# dcdc0210.net
KiCad netlist of a schematic drawn in EAGLE
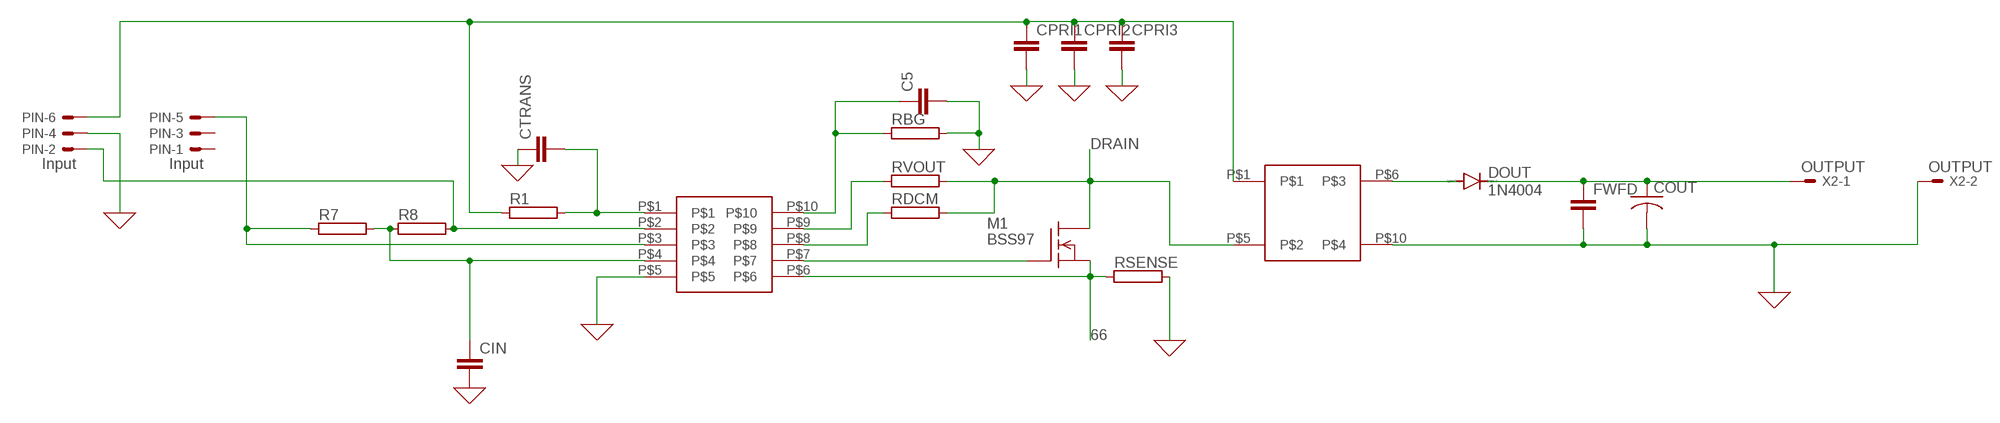
[diagram p0: schematic, sheet 1]

(export (version "E")
  (design (tool "Eeschema 10.0.6"))
  (components
    (comp (ref "C5")
      (value "C5/3.5")
      (footprint "eagle-import:C5B3.5")
      (libsource (lib "eagle-import") (part "C5/3.5"))
    )
    (comp (ref "CIN")
      (value "C5/3.5")
      (footprint "eagle-import:C5B3.5")
      (libsource (lib "eagle-import") (part "C5/3.5"))
    )
    (comp (ref "COUT")
      (value "C-US050-050X075")
      (footprint "eagle-import:C050-050X075")
      (libsource (lib "eagle-import") (part "C-US050-050X075"))
    )
    (comp (ref "CPRI1")
      (value "C5/3.5")
      (footprint "eagle-import:C5B3.5")
      (libsource (lib "eagle-import") (part "C5/3.5"))
    )
    (comp (ref "CPRI2")
      (value "C5/3.5")
      (footprint "eagle-import:C5B3.5")
      (libsource (lib "eagle-import") (part "C5/3.5"))
    )
    (comp (ref "CPRI3")
      (value "C5/3.5")
      (footprint "eagle-import:C5B3.5")
      (libsource (lib "eagle-import") (part "C5/3.5"))
    )
    (comp (ref "CTRANS")
      (value "C5/3.5")
      (footprint "eagle-import:C5B3.5")
      (libsource (lib "eagle-import") (part "C5/3.5"))
    )
    (comp (ref "DOUT")
      (value "1N4004")
      (footprint "eagle-import:DO41-10")
      (libsource (lib "eagle-import") (part "1N4004"))
    )
    (comp (ref "FWFD")
      (value "C5/3.5")
      (footprint "eagle-import:C5B3.5")
      (libsource (lib "eagle-import") (part "C5/3.5"))
    )
    (comp (ref "M1")
      (value "BSS97")
      (footprint "eagle-import:TO202")
      (libsource (lib "eagle-import") (part "BSS97"))
    )
    (comp (ref "PIN")
      (value "Input")
      (footprint "eagle-import:332-06")
      (libsource (lib "eagle-import") (part "332-06"))
    )
    (comp (ref "R1")
      (value "RAC01")
      (footprint "eagle-import:AC01")
      (libsource (lib "eagle-import") (part "RAC01"))
    )
    (comp (ref "R7")
      (value "RAC01")
      (footprint "eagle-import:AC01")
      (libsource (lib "eagle-import") (part "RAC01"))
    )
    (comp (ref "R8")
      (value "RAC01")
      (footprint "eagle-import:AC01")
      (libsource (lib "eagle-import") (part "RAC01"))
    )
    (comp (ref "RBG")
      (value "RAC01")
      (footprint "eagle-import:AC01")
      (libsource (lib "eagle-import") (part "RAC01"))
    )
    (comp (ref "RDCM")
      (value "RAC01")
      (footprint "eagle-import:AC01")
      (libsource (lib "eagle-import") (part "RAC01"))
    )
    (comp (ref "RSENSE")
      (value "RAC01")
      (footprint "eagle-import:AC01")
      (libsource (lib "eagle-import") (part "RAC01"))
    )
    (comp (ref "RVOUT")
      (value "RAC01")
      (footprint "eagle-import:AC01")
      (libsource (lib "eagle-import") (part "RAC01"))
    )
    (comp (ref "U$1")
      (value "LT3750")
      (footprint "eagle-import:LT3750")
      (libsource (lib "eagle-import") (part "LT3750"))
    )
    (comp (ref "U$2")
      (value "32052")
      (footprint "eagle-import:32052")
      (libsource (lib "eagle-import") (part "32052"))
    )
    (comp (ref "X2")
      (value "OUTPUT")
      (footprint "eagle-import:332-02")
      (libsource (lib "eagle-import") (part "332-02"))
    )
  )
  (nets
    (net (code "1") (name "/66") (class "Default")
      (node (ref "M1") (pin "1") (pinfunction "S_1") (pintype "passive"))
      (node (ref "RSENSE") (pin "1") (pinfunction "1_1") (pintype "passive"))
      (node (ref "U$1") (pin "P$6") (pinfunction "P$6_P$6") (pintype "bidirectional"))
    )
    (net (code "2") (name "/DRAIN") (class "Default")
      (node (ref "M1") (pin "2") (pinfunction "D_2") (pintype "passive"))
      (node (ref "RDCM") (pin "2") (pinfunction "2_2") (pintype "passive"))
      (node (ref "RVOUT") (pin "2") (pinfunction "2_2") (pintype "passive"))
      (node (ref "U$2") (pin "P$5") (pinfunction "P$2_P$5") (pintype "bidirectional"))
    )
    (net (code "3") (name "GND") (class "Default")
      (node (ref "C5") (pin "2") (pinfunction "2_2") (pintype "passive"))
      (node (ref "CIN") (pin "2") (pinfunction "2_2") (pintype "passive"))
      (node (ref "COUT") (pin "2") (pinfunction "2_2") (pintype "passive"))
      (node (ref "CPRI1") (pin "2") (pinfunction "2_2") (pintype "passive"))
      (node (ref "CPRI2") (pin "2") (pinfunction "2_2") (pintype "passive"))
      (node (ref "CPRI3") (pin "2") (pinfunction "2_2") (pintype "passive"))
      (node (ref "CTRANS") (pin "1") (pinfunction "1_1") (pintype "passive"))
      (node (ref "FWFD") (pin "2") (pinfunction "2_2") (pintype "passive"))
      (node (ref "PIN") (pin "4") (pinfunction "S_4") (pintype "passive"))
      (node (ref "RBG") (pin "2") (pinfunction "2_2") (pintype "passive"))
      (node (ref "RSENSE") (pin "2") (pinfunction "2_2") (pintype "passive"))
      (node (ref "U$1") (pin "P$5") (pinfunction "P$5_P$5") (pintype "bidirectional"))
      (node (ref "U$2") (pin "P$10") (pinfunction "P$4_P$10") (pintype "bidirectional"))
      (node (ref "X2") (pin "2") (pinfunction "S_2") (pintype "passive"))
    )
    (net (code "4") (name "Net-(C5-Pad1)") (class "Default")
      (node (ref "C5") (pin "1") (pinfunction "1_1") (pintype "passive"))
      (node (ref "RBG") (pin "1") (pinfunction "1_1") (pintype "passive"))
      (node (ref "U$1") (pin "P$10") (pinfunction "P$10_P$10") (pintype "bidirectional"))
    )
    (net (code "5") (name "Net-(CIN-Pad1)") (class "Default")
      (node (ref "CIN") (pin "1") (pinfunction "1_1") (pintype "passive"))
      (node (ref "R7") (pin "2") (pinfunction "2_2") (pintype "passive"))
      (node (ref "R8") (pin "1") (pinfunction "1_1") (pintype "passive"))
      (node (ref "U$1") (pin "P$4") (pinfunction "P$4_P$4") (pintype "bidirectional"))
    )
    (net (code "6") (name "Net-(CTRANS-Pad2)") (class "Default")
      (node (ref "CTRANS") (pin "2") (pinfunction "2_2") (pintype "passive"))
      (node (ref "R1") (pin "2") (pinfunction "2_2") (pintype "passive"))
      (node (ref "U$1") (pin "P$1") (pinfunction "P$1_P$1") (pintype "bidirectional"))
    )
    (net (code "7") (name "Net-(M1-G)") (class "Default")
      (node (ref "M1") (pin "3") (pinfunction "G_3") (pintype "passive"))
      (node (ref "U$1") (pin "P$7") (pinfunction "P$7_P$7") (pintype "bidirectional"))
    )
    (net (code "8") (name "Net-(PINB-S)") (class "Default")
      (node (ref "PIN") (pin "2") (pinfunction "S_2") (pintype "passive"))
      (node (ref "R8") (pin "2") (pinfunction "2_2") (pintype "passive"))
      (node (ref "U$1") (pin "P$2") (pinfunction "P$2_P$2") (pintype "bidirectional"))
    )
    (net (code "9") (name "Net-(PINE-S)") (class "Default")
      (node (ref "PIN") (pin "5") (pinfunction "S_5") (pintype "passive"))
      (node (ref "R7") (pin "1") (pinfunction "1_1") (pintype "passive"))
      (node (ref "U$1") (pin "P$3") (pinfunction "P$3_P$3") (pintype "bidirectional"))
    )
    (net (code "10") (name "Net-(PINF-S)") (class "Default")
      (node (ref "CPRI1") (pin "1") (pinfunction "1_1") (pintype "passive"))
      (node (ref "CPRI2") (pin "1") (pinfunction "1_1") (pintype "passive"))
      (node (ref "CPRI3") (pin "1") (pinfunction "1_1") (pintype "passive"))
      (node (ref "PIN") (pin "6") (pinfunction "S_6") (pintype "passive"))
      (node (ref "R1") (pin "1") (pinfunction "1_1") (pintype "passive"))
      (node (ref "U$2") (pin "P$1") (pinfunction "P$1_P$1") (pintype "bidirectional"))
    )
    (net (code "11") (name "Net-(RDCM-Pad1)") (class "Default")
      (node (ref "RDCM") (pin "1") (pinfunction "1_1") (pintype "passive"))
      (node (ref "U$1") (pin "P$8") (pinfunction "P$8_P$8") (pintype "bidirectional"))
    )
    (net (code "12") (name "Net-(RVOUT-Pad1)") (class "Default")
      (node (ref "RVOUT") (pin "1") (pinfunction "1_1") (pintype "passive"))
      (node (ref "U$1") (pin "P$9") (pinfunction "P$9_P$9") (pintype "bidirectional"))
    )
    (net (code "13") (name "Net-(U$2-P$3)") (class "Default")
      (node (ref "DOUT") (pin "A") (pinfunction "A_A") (pintype "passive"))
      (node (ref "U$2") (pin "P$6") (pinfunction "P$3_P$6") (pintype "bidirectional"))
    )
    (net (code "14") (name "Net-(X2A-S)") (class "Default")
      (node (ref "COUT") (pin "1") (pinfunction "1_1") (pintype "passive"))
      (node (ref "DOUT") (pin "C") (pinfunction "C_C") (pintype "passive"))
      (node (ref "FWFD") (pin "1") (pinfunction "1_1") (pintype "passive"))
      (node (ref "X2") (pin "1") (pinfunction "S_1") (pintype "passive"))
    )
    (net (code "15") (name "unconnected-(PINA-S-Pad1)") (class "Default")
      (node (ref "PIN") (pin "1") (pinfunction "S_1") (pintype "passive"))
    )
    (net (code "16") (name "unconnected-(PINC-S-Pad3)") (class "Default")
      (node (ref "PIN") (pin "3") (pinfunction "S_3") (pintype "passive"))
    )
  )
)
